# SixAxIMU_XSens.net
KiCad netlist of a schematic drawn in Altium Designer
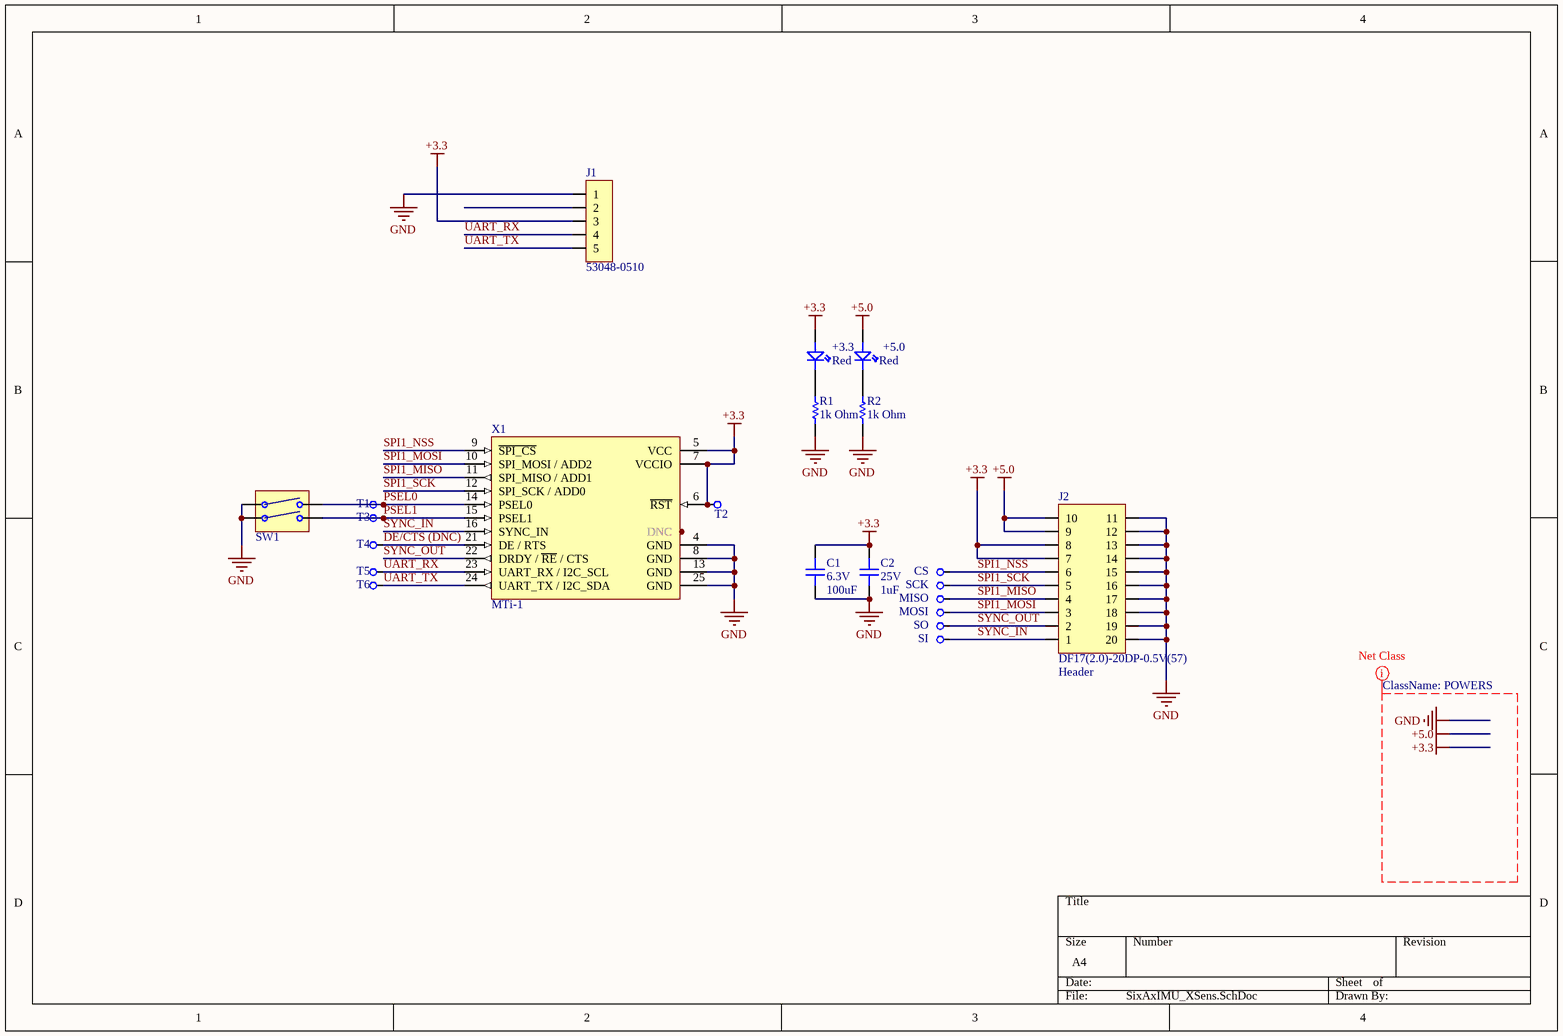
[diagram p0: SixAxIMU_XSens.SchDoc]

(export (version "E")
  (design (tool "Eeschema 10.0.6"))
  (components
    (comp (ref "+3.3")
      (value "Red")
      (footprint "LED 0603")
      (description "LED, Red, 0603")
      (fields (field (name "MANUFACTURER PART NUMBER") "1608SURC-06"))
      (libsource (lib "NaniBox") (part "1608SURC-06"))
    )
    (comp (ref "+5.0")
      (value "Red")
      (footprint "LED 0603")
      (description "LED, Red, 0603")
      (fields (field (name "MANUFACTURER PART NUMBER") "1608SURC-06"))
      (libsource (lib "NaniBox") (part "1608SURC-06"))
    )
    (comp (ref "C1")
      (value "100uF")
      (footprint "CAP 1206")
      (description "MLCC, 100uF, 1206, 20%, 6.3V, X5R")
      (fields
        (field (name "MANUFACTURER") "Samsung")
        (field (name "MANUFACTURER PART NUMBER") "CL31A107MQHNNNE")
        (field (name "VOLTAGE RATING") "6.3V")
      )
      (libsource (lib "NaniBox") (part "CL31A107MQHNNNE"))
    )
    (comp (ref "C2")
      (value "1uF")
      (footprint "CAP 0603")
      (description "MLCC, 1uF, 0603, 10%, 25V, X5R")
      (fields
        (field (name "MANUFACTURER") "Samsung")
        (field (name "MANUFACTURER PART NUMBER") "CL10A105KA8NNNC")
        (field (name "VOLTAGE RATING") "25V")
      )
      (libsource (lib "NaniBox") (part "CL10A105KA8NNNC"))
    )
    (comp (ref "CS")
      (value "TEST")
      (footprint "TEST_0.5mm, SMD")
      (libsource (lib "NaniBox_Conn") (part "TEST"))
    )
    (comp (ref "J1")
      (value "53048-0510")
      (footprint "PicoBlade, 53048-0510")
      (description "PicoBlade, Header, R/A, PTH, 5 Pos, 1.25mm Pitch")
      (fields (field (name "MANUFACTURER") "Molex"))
      (libsource (lib "NaniBox_Conn") (part "53048-0510"))
    )
    (comp (ref "J2")
      (value "DF17(2.0)-20DP-0.5V(57)")
      (footprint "DF17(2.0)-20DP-0.5V(57)")
      (description "Conn, B2B, 20 Pos, HEADER")
      (fields (field (name "MANUFACTURER") "Hirose") (field (name "TYPE") "Header"))
      (libsource (lib "NaniBox") (part "DF17(2.0)-20DP-0.5V(57)"))
    )
    (comp (ref "MISO")
      (value "TEST")
      (footprint "TEST_0.5mm, SMD")
      (libsource (lib "NaniBox_Conn") (part "TEST"))
    )
    (comp (ref "MOSI")
      (value "TEST")
      (footprint "TEST_0.5mm, SMD")
      (libsource (lib "NaniBox_Conn") (part "TEST"))
    )
    (comp (ref "R1")
      (value "1k Ohm")
      (footprint "RES 0402")
      (description "RES, 0402, 1k, 1%")
      (fields
        (field (name "MANUFACTURER") "Yageo")
        (field (name "MANUFACTURER PART NUMBER") "P311-1.00KLRTR-ND")
      )
      (libsource (lib "NaniBox") (part "P311-1.00KLRTR-ND"))
    )
    (comp (ref "R2")
      (value "1k Ohm")
      (footprint "RES 0402")
      (description "RES, 0402, 1k, 1%")
      (fields
        (field (name "MANUFACTURER") "Yageo")
        (field (name "MANUFACTURER PART NUMBER") "P311-1.00KLRTR-ND")
      )
      (libsource (lib "NaniBox") (part "P311-1.00KLRTR-ND"))
    )
    (comp (ref "SCK")
      (value "TEST")
      (footprint "TEST_0.5mm, SMD")
      (libsource (lib "NaniBox_Conn") (part "TEST"))
    )
    (comp (ref "SI")
      (value "TEST")
      (footprint "TEST_0.5mm, SMD")
      (libsource (lib "NaniBox_Conn") (part "TEST"))
    )
    (comp (ref "SO")
      (value "TEST")
      (footprint "TEST_0.5mm, SMD")
      (libsource (lib "NaniBox_Conn") (part "TEST"))
    )
    (comp (ref "SW1")
      (value "GDH02STR04")
      (footprint "GDH02STR04")
      (description "DIP Switch, 2 POS, SMD")
      (fields (field (name "MANUFACTURER") "TE Connectivity"))
      (libsource (lib "NaniBox") (part "GDH02STR04"))
    )
    (comp (ref "T1")
      (value "TEST")
      (footprint "TEST_0.5mm, SMD")
      (libsource (lib "NaniBox_Conn") (part "TEST"))
    )
    (comp (ref "T2")
      (value "TEST")
      (footprint "TEST_0.5mm, SMD")
      (libsource (lib "NaniBox_Conn") (part "TEST"))
    )
    (comp (ref "T3")
      (value "TEST")
      (footprint "TEST_0.5mm, SMD")
      (libsource (lib "NaniBox_Conn") (part "TEST"))
    )
    (comp (ref "T4")
      (value "TEST")
      (footprint "TEST_0.5mm, SMD")
      (libsource (lib "NaniBox_Conn") (part "TEST"))
    )
    (comp (ref "T5")
      (value "TEST")
      (footprint "TEST_0.5mm, SMD")
      (libsource (lib "NaniBox_Conn") (part "TEST"))
    )
    (comp (ref "T6")
      (value "TEST")
      (footprint "TEST_0.5mm, SMD")
      (libsource (lib "NaniBox_Conn") (part "TEST"))
    )
    (comp (ref "X1")
      (value "MTi-1")
      (footprint "PLCC28 - XSens MTi-1 Special")
      (description "XSens MTi-1 Series")
      (fields (field (name "MANUFACTURER") "XSens"))
      (libsource (lib "NaniBox") (part "MTi-1"))
    )
  )
  (nets
    (net (code "1") (name "+3.3") (class "Default")
      (node (ref "+3.3") (pin "A") (pinfunction "A_A") (pintype "power_in"))
      (node (ref "C1") (pin "2") (pinfunction "2_2") (pintype "passive"))
      (node (ref "C2") (pin "2") (pinfunction "2_2") (pintype "passive"))
      (node (ref "J1") (pin "3") (pinfunction "3_3") (pintype "passive"))
      (node (ref "J2") (pin "7") (pinfunction "7_7") (pintype "passive"))
      (node (ref "J2") (pin "8") (pinfunction "8_8") (pintype "passive"))
      (node (ref "T2") (pin "0") (pinfunction "0_0") (pintype "passive"))
      (node (ref "X1") (pin "5") (pinfunction "VCC_5") (pintype "power_in"))
      (node (ref "X1") (pin "6") (pinfunction "RST_6") (pintype "input"))
      (node (ref "X1") (pin "7") (pinfunction "VCCIO_7") (pintype "power_in"))
    )
    (net (code "2") (name "+5.0") (class "Default")
      (node (ref "+5.0") (pin "A") (pinfunction "A_A") (pintype "power_in"))
      (node (ref "J2") (pin "10") (pinfunction "10_10") (pintype "passive"))
      (node (ref "J2") (pin "9") (pinfunction "9_9") (pintype "passive"))
    )
    (net (code "3") (name "/DE{slash}CTS (DNC)") (class "Default")
      (node (ref "T4") (pin "0") (pinfunction "0_0") (pintype "passive"))
      (node (ref "X1") (pin "21") (pinfunction "DE_/_RTS_21") (pintype "input"))
    )
    (net (code "4") (name "/PSEL0") (class "Default")
      (node (ref "SW1") (pin "2") (pinfunction "2_2") (pintype "passive"))
      (node (ref "T1") (pin "0") (pinfunction "0_0") (pintype "passive"))
      (node (ref "X1") (pin "14") (pinfunction "PSEL0_14") (pintype "input"))
    )
    (net (code "5") (name "/PSEL1") (class "Default")
      (node (ref "SW1") (pin "4") (pinfunction "4_4") (pintype "passive"))
      (node (ref "T3") (pin "0") (pinfunction "0_0") (pintype "passive"))
      (node (ref "X1") (pin "15") (pinfunction "PSEL1_15") (pintype "input"))
    )
    (net (code "6") (name "/SPI1_MISO") (class "Default")
      (node (ref "J2") (pin "4") (pinfunction "4_4") (pintype "passive"))
      (node (ref "MISO") (pin "0") (pinfunction "0_0") (pintype "passive"))
      (node (ref "X1") (pin "11") (pinfunction "SPI_MISO_/_ADD1_11") (pintype "output"))
    )
    (net (code "7") (name "/SPI1_MOSI") (class "Default")
      (node (ref "J2") (pin "3") (pinfunction "3_3") (pintype "passive"))
      (node (ref "MOSI") (pin "0") (pinfunction "0_0") (pintype "passive"))
      (node (ref "X1") (pin "10") (pinfunction "SPI_MOSI_/_ADD2_10") (pintype "input"))
    )
    (net (code "8") (name "/SPI1_NSS") (class "Default")
      (node (ref "CS") (pin "0") (pinfunction "0_0") (pintype "passive"))
      (node (ref "J2") (pin "6") (pinfunction "6_6") (pintype "passive"))
      (node (ref "X1") (pin "9") (pinfunction "SPI_CS_9") (pintype "input"))
    )
    (net (code "9") (name "/SPI1_SCK") (class "Default")
      (node (ref "J2") (pin "5") (pinfunction "5_5") (pintype "passive"))
      (node (ref "SCK") (pin "0") (pinfunction "0_0") (pintype "passive"))
      (node (ref "X1") (pin "12") (pinfunction "SPI_SCK_/_ADD0_12") (pintype "input"))
    )
    (net (code "10") (name "/SYNC_IN") (class "Default")
      (node (ref "J2") (pin "1") (pinfunction "1_1") (pintype "passive"))
      (node (ref "SI") (pin "0") (pinfunction "0_0") (pintype "passive"))
      (node (ref "X1") (pin "16") (pinfunction "SYNC_IN_16") (pintype "input"))
    )
    (net (code "11") (name "/SYNC_OUT") (class "Default")
      (node (ref "J2") (pin "2") (pinfunction "2_2") (pintype "passive"))
      (node (ref "SO") (pin "0") (pinfunction "0_0") (pintype "passive"))
      (node (ref "X1") (pin "22") (pinfunction "DRDY_/_~{RE}_/_CTS_22") (pintype "output"))
    )
    (net (code "12") (name "/UART_RX") (class "Default")
      (node (ref "J1") (pin "4") (pinfunction "4_4") (pintype "passive"))
      (node (ref "T5") (pin "0") (pinfunction "0_0") (pintype "passive"))
      (node (ref "X1") (pin "23") (pinfunction "UART_RX_/_I2C_SCL_23") (pintype "input"))
    )
    (net (code "13") (name "/UART_TX") (class "Default")
      (node (ref "J1") (pin "5") (pinfunction "5_5") (pintype "passive"))
      (node (ref "T6") (pin "0") (pinfunction "0_0") (pintype "passive"))
      (node (ref "X1") (pin "24") (pinfunction "UART_TX_/_I2C_SDA_24") (pintype "output"))
    )
    (net (code "14") (name "GND") (class "Default")
      (node (ref "C1") (pin "1") (pinfunction "1_1") (pintype "passive"))
      (node (ref "C2") (pin "1") (pinfunction "1_1") (pintype "passive"))
      (node (ref "J1") (pin "1") (pinfunction "1_1") (pintype "passive"))
      (node (ref "J2") (pin "11") (pinfunction "11_11") (pintype "passive"))
      (node (ref "J2") (pin "12") (pinfunction "12_12") (pintype "passive"))
      (node (ref "J2") (pin "13") (pinfunction "13_13") (pintype "passive"))
      (node (ref "J2") (pin "14") (pinfunction "14_14") (pintype "passive"))
      (node (ref "J2") (pin "15") (pinfunction "15_15") (pintype "passive"))
      (node (ref "J2") (pin "16") (pinfunction "16_16") (pintype "passive"))
      (node (ref "J2") (pin "17") (pinfunction "17_17") (pintype "passive"))
      (node (ref "J2") (pin "18") (pinfunction "18_18") (pintype "passive"))
      (node (ref "J2") (pin "19") (pinfunction "19_19") (pintype "passive"))
      (node (ref "J2") (pin "20") (pinfunction "20_20") (pintype "passive"))
      (node (ref "R1") (pin "1") (pinfunction "1_1") (pintype "passive"))
      (node (ref "R2") (pin "1") (pinfunction "1_1") (pintype "passive"))
      (node (ref "SW1") (pin "1") (pinfunction "1_1") (pintype "passive"))
      (node (ref "SW1") (pin "3") (pinfunction "3_3") (pintype "passive"))
      (node (ref "X1") (pin "13") (pinfunction "GND_13") (pintype "power_in"))
      (node (ref "X1") (pin "25") (pinfunction "GND_25") (pintype "power_in"))
      (node (ref "X1") (pin "4") (pinfunction "GND_4") (pintype "power_in"))
      (node (ref "X1") (pin "8") (pinfunction "GND_8") (pintype "power_in"))
    )
    (net (code "15") (name "Net-(+3.3-PadK)") (class "Default")
      (node (ref "+3.3") (pin "K") (pinfunction "K_K") (pintype "power_in"))
      (node (ref "R1") (pin "2") (pinfunction "2_2") (pintype "passive"))
    )
    (net (code "16") (name "Net-(+5.0-PadK)") (class "Default")
      (node (ref "+5.0") (pin "K") (pinfunction "K_K") (pintype "power_in"))
      (node (ref "R2") (pin "2") (pinfunction "2_2") (pintype "passive"))
    )
    (net (code "17") (name "Net-(X1-DNC-Pad1)") (class "Default")
      (node (ref "X1") (pin "1") (pinfunction "DNC_1") (pintype "passive"))
      (node (ref "X1") (pin "17") (pinfunction "DNC_17") (pintype "passive"))
      (node (ref "X1") (pin "18") (pinfunction "DNC_18") (pintype "passive"))
      (node (ref "X1") (pin "19") (pinfunction "DNC_19") (pintype "passive"))
      (node (ref "X1") (pin "2") (pinfunction "DNC_2") (pintype "passive"))
      (node (ref "X1") (pin "20") (pinfunction "DNC_20") (pintype "passive"))
      (node (ref "X1") (pin "26") (pinfunction "DNC_26") (pintype "passive"))
      (node (ref "X1") (pin "27") (pinfunction "DNC_27") (pintype "passive"))
      (node (ref "X1") (pin "28") (pinfunction "DNC_28") (pintype "passive"))
      (node (ref "X1") (pin "3") (pinfunction "DNC_3") (pintype "passive"))
    )
    (net (code "18") (name "unconnected-(J1-Pad2)") (class "Default")
      (node (ref "J1") (pin "2") (pinfunction "2_2") (pintype "passive"))
    )
  )
)
